# Nova_Board_Sheet.net
KiCad netlist of a schematic drawn in Altium Designer
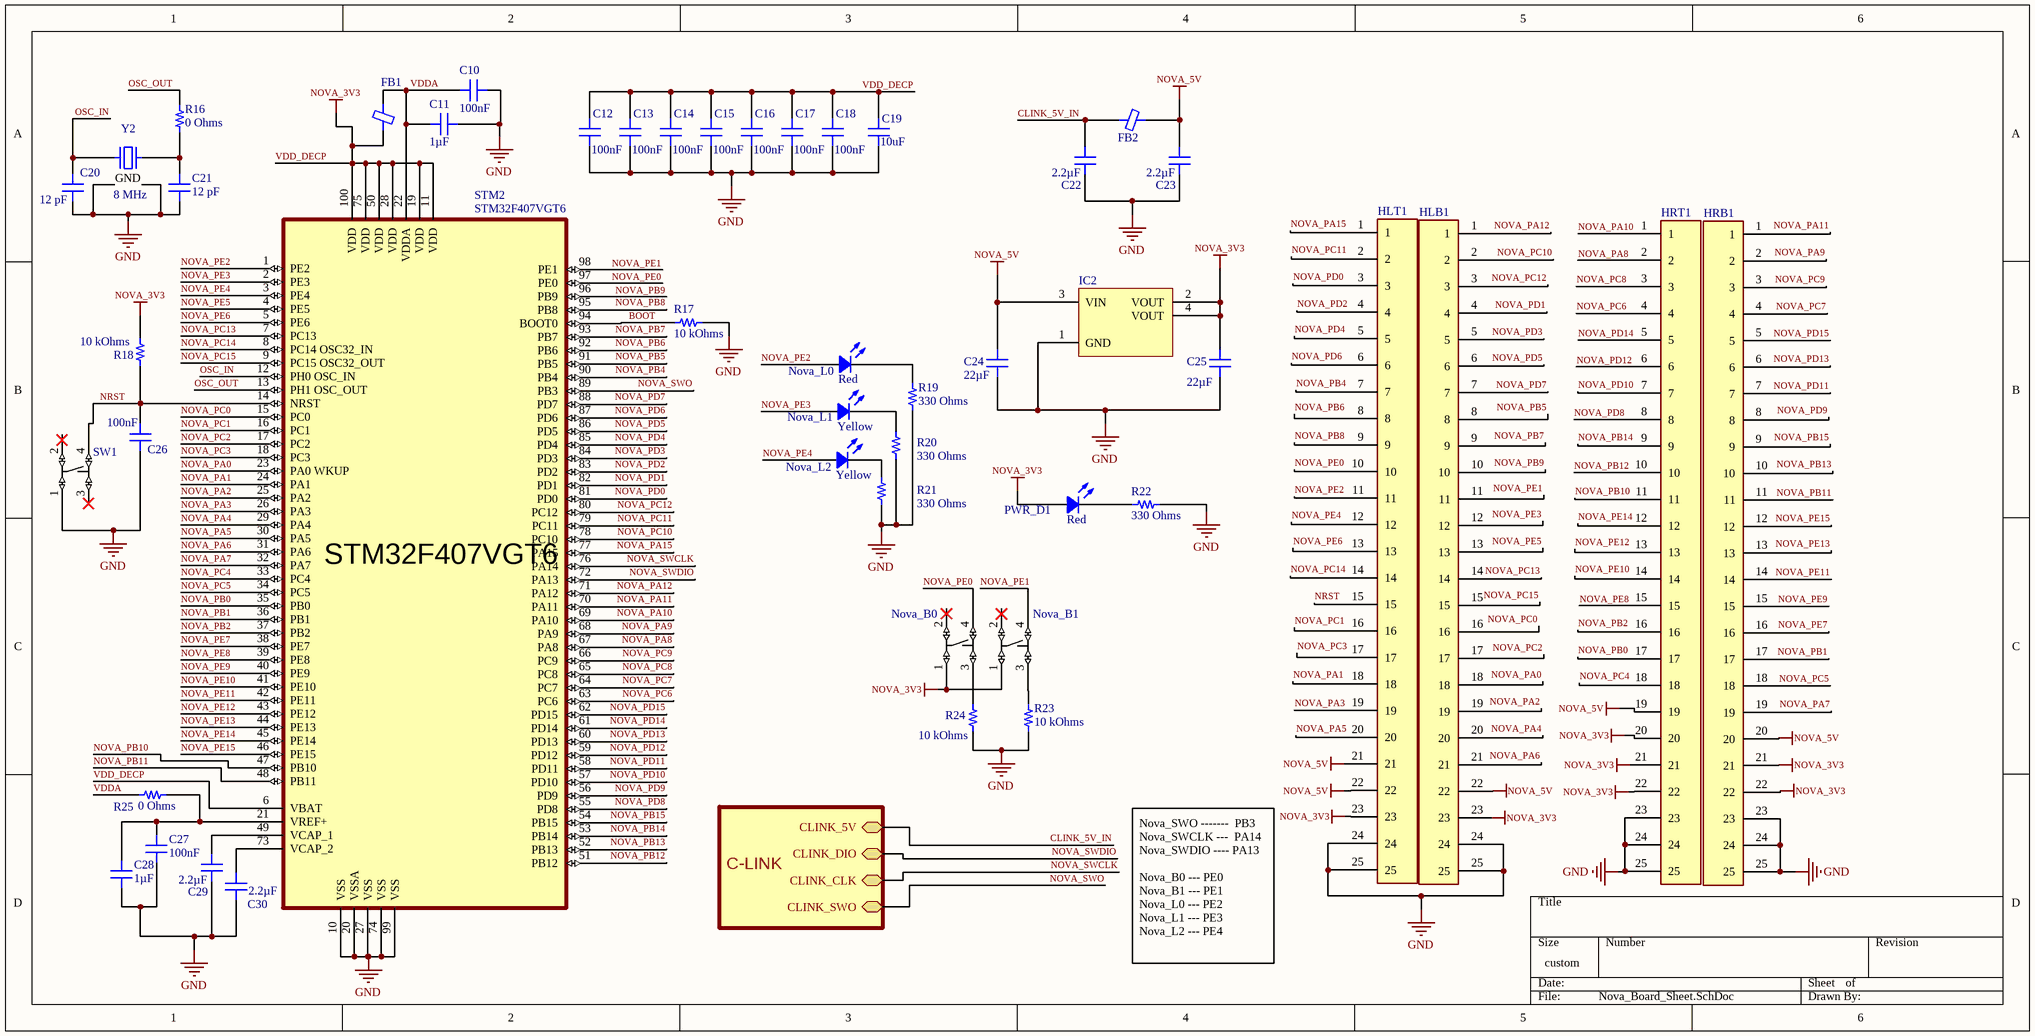
[diagram p0: Nova_Board_Sheet.SchDoc]

(export (version "E")
  (design (tool "Eeschema 10.0.6"))
  (components
    (comp (ref "C10")
      (value "0.1µF")
      (footprint "CAP 0603_1608")
      (description "CAP CER 0.1UF 100V X7R 0603")
      (fields
        (field (name "PART NUMBER") "06031C104KAT2A")
        (field (name "CAPACITANCE") "100nF")
        (field (name "MANUFACTURER") "AVX Corporation")
      )
      (libsource (lib "Celestial Altium Library - altium_library") (part "Capacitor"))
    )
    (comp (ref "C11")
      (value "1µF")
      (footprint "CAP 0603_1608")
      (description "CAP CER 0.1UF 100V X7R 0603")
      (fields
        (field (name "PART NUMBER") "06031C104KAT2A")
        (field (name "CAPACITANCE") "1µF")
        (field (name "MANUFACTURER") "AVX Corporation")
      )
      (libsource (lib "Celestial Altium Library - altium_library") (part "Capacitor"))
    )
    (comp (ref "C12")
      (value "0.1µF")
      (footprint "CAP 0603_1608")
      (description "CAP CER 0.1UF 100V X7R 0603")
      (fields
        (field (name "PART NUMBER") "06031C104KAT2A")
        (field (name "CAPACITANCE") "100nF")
        (field (name "MANUFACTURER") "AVX Corporation")
      )
      (libsource (lib "Celestial Altium Library - altium_library") (part "Capacitor"))
    )
    (comp (ref "C13")
      (value "0.1µF")
      (footprint "CAP 0603_1608")
      (description "CAP CER 0.1UF 100V X7R 0603")
      (fields
        (field (name "PART NUMBER") "06031C104KAT2A")
        (field (name "CAPACITANCE") "100nF")
        (field (name "MANUFACTURER") "AVX Corporation")
      )
      (libsource (lib "Celestial Altium Library - altium_library") (part "Capacitor"))
    )
    (comp (ref "C14")
      (value "0.1µF")
      (footprint "CAP 0603_1608")
      (description "CAP CER 0.1UF 100V X7R 0603")
      (fields
        (field (name "PART NUMBER") "06031C104KAT2A")
        (field (name "CAPACITANCE") "100nF")
        (field (name "MANUFACTURER") "AVX Corporation")
      )
      (libsource (lib "Celestial Altium Library - altium_library") (part "Capacitor"))
    )
    (comp (ref "C15")
      (value "0.1µF")
      (footprint "CAP 0603_1608")
      (description "CAP CER 0.1UF 100V X7R 0603")
      (fields
        (field (name "PART NUMBER") "06031C104KAT2A")
        (field (name "CAPACITANCE") "100nF")
        (field (name "MANUFACTURER") "AVX Corporation")
      )
      (libsource (lib "Celestial Altium Library - altium_library") (part "Capacitor"))
    )
    (comp (ref "C16")
      (value "0.1µF")
      (footprint "CAP 0603_1608")
      (description "CAP CER 0.1UF 100V X7R 0603")
      (fields
        (field (name "PART NUMBER") "06031C104KAT2A")
        (field (name "CAPACITANCE") "100nF")
        (field (name "MANUFACTURER") "AVX Corporation")
      )
      (libsource (lib "Celestial Altium Library - altium_library") (part "Capacitor"))
    )
    (comp (ref "C17")
      (value "0.1µF")
      (footprint "CAP 0603_1608")
      (description "CAP CER 0.1UF 100V X7R 0603")
      (fields
        (field (name "PART NUMBER") "06031C104KAT2A")
        (field (name "CAPACITANCE") "100nF")
        (field (name "MANUFACTURER") "AVX Corporation")
      )
      (libsource (lib "Celestial Altium Library - altium_library") (part "Capacitor"))
    )
    (comp (ref "C18")
      (value "0.1µF")
      (footprint "CAP 0603_1608")
      (description "CAP CER 0.1UF 100V X7R 0603")
      (fields
        (field (name "PART NUMBER") "06031C104KAT2A")
        (field (name "CAPACITANCE") "100nF")
        (field (name "MANUFACTURER") "AVX Corporation")
      )
      (libsource (lib "Celestial Altium Library - altium_library") (part "Capacitor"))
    )
    (comp (ref "C19")
      (value "10µF")
      (footprint "CAP 0603_1608")
      (description "CAP CER 0.1UF 100V X7R 0603")
      (fields
        (field (name "PART NUMBER") "06031C104KAT2A")
        (field (name "CAPACITANCE") "10uF")
        (field (name "MANUFACTURER") "AVX Corporation")
      )
      (libsource (lib "Celestial Altium Library - altium_library") (part "Capacitor"))
    )
    (comp (ref "C20")
      (value "12 pF")
      (footprint "CAP 0603_1608")
      (description "HIGH-Q MLCC (CF): 0603, 22 PF (1")
      (fields
        (field (name "PART NUMBER") "C06CF220F-9ZN-X0T")
        (field (name "CAPACITANCE") "12 pF")
        (field (name "MANUFACTURER") "Knowles Dielectric Labs")
      )
      (libsource (lib "Celestial Altium Library - altium_library") (part "Capacitor"))
    )
    (comp (ref "C21")
      (value "12 pF")
      (footprint "CAP 0603_1608")
      (description "HIGH-Q MLCC (CF): 0603, 22 PF (1")
      (fields
        (field (name "PART NUMBER") "C06CF220F-9ZN-X0T")
        (field (name "CAPACITANCE") "12 pF")
        (field (name "MANUFACTURER") "Knowles Dielectric Labs")
      )
      (libsource (lib "Celestial Altium Library - altium_library") (part "Capacitor"))
    )
    (comp (ref "C22")
      (value "2.2µF")
      (footprint "CAP 0603_1608")
      (description "CAP CER 0.1UF 100V X7R 0603")
      (fields
        (field (name "PART NUMBER") "06031C104KAT2A")
        (field (name "CAPACITANCE") "2.2µF")
        (field (name "MANUFACTURER") "AVX Corporation")
      )
      (libsource (lib "Celestial Altium Library - altium_library") (part "Capacitor"))
    )
    (comp (ref "C23")
      (value "2.2µF")
      (footprint "CAP 0603_1608")
      (description "CAP CER 0.1UF 100V X7R 0603")
      (fields
        (field (name "PART NUMBER") "06031C104KAT2A")
        (field (name "CAPACITANCE") "2.2µF")
        (field (name "MANUFACTURER") "AVX Corporation")
      )
      (libsource (lib "Celestial Altium Library - altium_library") (part "Capacitor"))
    )
    (comp (ref "C24")
      (value "22µF")
      (footprint "CAP 0805_2012")
      (description "CAP CER 22UF 10V X5R 0805")
      (fields
        (field (name "PART NUMBER") "0805ZD226MAT2A")
        (field (name "CAPACITANCE") "22µF")
        (field (name "MANUFACTURER") "AVX Corporation")
      )
      (libsource (lib "Celestial Altium Library - altium_library") (part "Capacitor"))
    )
    (comp (ref "C25")
      (value "22µF")
      (footprint "CAP 0805_2012")
      (description "CAP CER 22UF 10V X5R 0805")
      (fields
        (field (name "PART NUMBER") "0805ZD226MAT2A")
        (field (name "CAPACITANCE") "22µF")
        (field (name "MANUFACTURER") "AVX Corporation")
      )
      (libsource (lib "Celestial Altium Library - altium_library") (part "Capacitor"))
    )
    (comp (ref "C26")
      (value "0.1µF")
      (footprint "CAP 0603_1608")
      (description "CAP CER 0.1UF 100V X7R 0603")
      (fields
        (field (name "PART NUMBER") "06031C104KAT2A")
        (field (name "CAPACITANCE") "100nF")
        (field (name "MANUFACTURER") "AVX Corporation")
      )
      (libsource (lib "Celestial Altium Library - altium_library") (part "Capacitor"))
    )
    (comp (ref "C27")
      (value "0.1µF")
      (footprint "CAP 0603_1608")
      (description "CAP CER 0.1UF 100V X7R 0603")
      (fields
        (field (name "PART NUMBER") "06031C104KAT2A")
        (field (name "CAPACITANCE") "100nF")
        (field (name "MANUFACTURER") "AVX Corporation")
      )
      (libsource (lib "Celestial Altium Library - altium_library") (part "Capacitor"))
    )
    (comp (ref "C28")
      (value "1µF")
      (footprint "CAP 0603_1608")
      (description "CAP CER 0.1UF 100V X7R 0603")
      (fields
        (field (name "PART NUMBER") "06031C104KAT2A")
        (field (name "CAPACITANCE") "1µF")
        (field (name "MANUFACTURER") "AVX Corporation")
      )
      (libsource (lib "Celestial Altium Library - altium_library") (part "Capacitor"))
    )
    (comp (ref "C29")
      (value "2.2µF")
      (footprint "CAP 0603_1608")
      (description "CAP CER 0.1UF 100V X7R 0603")
      (fields
        (field (name "PART NUMBER") "06031C104KAT2A")
        (field (name "CAPACITANCE") "2.2µF")
        (field (name "MANUFACTURER") "AVX Corporation")
      )
      (libsource (lib "Celestial Altium Library - altium_library") (part "Capacitor"))
    )
    (comp (ref "C30")
      (value "2.2µF")
      (footprint "CAP 0603_1608")
      (description "CAP CER 0.1UF 100V X7R 0603")
      (fields
        (field (name "PART NUMBER") "06031C104KAT2A")
        (field (name "CAPACITANCE") "2.2µF")
        (field (name "MANUFACTURER") "AVX Corporation")
      )
      (libsource (lib "Celestial Altium Library - altium_library") (part "Capacitor"))
    )
    (comp (ref "FB1")
      (value "600 Ohms @ 100MHz")
      (footprint "FER 0603_1608")
      (description "FERRITEBEAD SMD Z100MHZ=600OHM 7")
      (fields
        (field (name "PART NUMBER") "BLM18DN601SZ1D")
        (field (name "MANUFACTURER") "Murata Electronics")
      )
      (libsource (lib "Celestial Altium Library - altium_library") (part "Ferrite Chip"))
    )
    (comp (ref "FB2")
      (value "600 Ohms @ 100MHz")
      (footprint "FER 0603_1608")
      (description "FERRITEBEAD SMD Z100MHZ=600OHM 7")
      (fields
        (field (name "PART NUMBER") "BLM18DN601SZ1D")
        (field (name "MANUFACTURER") "Murata Electronics")
      )
      (libsource (lib "Celestial Altium Library - altium_library") (part "Ferrite Chip"))
    )
    (comp (ref "HLB1")
      (value "2.54mm_TH_1x25_pin_header")
      (footprint "2.54mm_TH_1x25_pin_header")
      (libsource (lib "") (part "2.54mm_TH_1x25_pin_header_1"))
    )
    (comp (ref "HLT1")
      (value "2.54mm_TH_1x25_pin_header")
      (footprint "2.54mm_TH_1x25_pin_header")
      (libsource (lib "ARAF_PERSONAL_INTEGRATED_LIBRARY") (part "2.54mm_TH_1x25_pin_header"))
    )
    (comp (ref "HRB1")
      (value "2.54mm_TH_1x25_pin_header")
      (footprint "2.54mm_TH_1x25_pin_header")
      (libsource (lib "") (part "2.54mm_TH_1x25_pin_header_1"))
    )
    (comp (ref "HRT1")
      (value "2.54mm_TH_1x25_pin_header")
      (footprint "2.54mm_TH_1x25_pin_header")
      (libsource (lib "ARAF_PERSONAL_INTEGRATED_LIBRARY") (part "2.54mm_TH_1x25_pin_header"))
    )
    (comp (ref "IC2")
      (value "LDL1117S33R")
      (footprint "ST SOT-223")
      (description "IC REG LINEAR 3.3V 1.2A SOT223")
      (fields (field (name "MANUFACTURER") "STMicroelectronics"))
      (libsource (lib "Celestial Altium Library - altium_library") (part "ST LDL1117"))
    )
    (comp (ref "Nova_B0")
      (value "3x4x2.5_oval_switch")
      (footprint "3x4x2.5_oval_button_footprint")
      (libsource (lib "PushButton_Series_SCH_Library_ARAF") (part "3x4x2.5_oval_switch"))
    )
    (comp (ref "Nova_B1")
      (value "3x4x2.5_oval_switch")
      (footprint "3x4x2.5_oval_button_footprint")
      (libsource (lib "PushButton_Series_SCH_Library_ARAF") (part "3x4x2.5_oval_switch"))
    )
    (comp (ref "Nova_L0")
      (value "Red")
      (footprint "LED 0603_1608 RED")
      (description "LED RED DIFFUSED 1608 SMD")
      (fields
        (field (name "PART NUMBER") "VFHR1111C-3BY2A-TR")
        (field (name "MANUFACTURER") "Stanley Electric Co")
      )
      (libsource (lib "Celestial Altium Library - altium_library") (part "LED"))
    )
    (comp (ref "Nova_L1")
      (value "Yellow")
      (footprint "LED 0603_1608 YELLOW")
      (description "LED YELLOW 0603 SMD")
      (fields (field (name "PART NUMBER") "5973405507F") (field (name "MANUFACTURER") "Dialight"))
      (libsource (lib "Celestial Altium Library - altium_library") (part "LED"))
    )
    (comp (ref "Nova_L2")
      (value "Yellow")
      (footprint "LED 0603_1608 YELLOW")
      (description "LED YELLOW 0603 SMD")
      (fields (field (name "PART NUMBER") "5973405507F") (field (name "MANUFACTURER") "Dialight"))
      (libsource (lib "Celestial Altium Library - altium_library") (part "LED"))
    )
    (comp (ref "PWR_D1")
      (value "Red")
      (footprint "LED 0603_1608 RED")
      (description "LED RED DIFFUSED 1608 SMD")
      (fields
        (field (name "PART NUMBER") "VFHR1111C-3BY2A-TR")
        (field (name "MANUFACTURER") "Stanley Electric Co")
      )
      (libsource (lib "Celestial Altium Library - altium_library") (part "LED"))
    )
    (comp (ref "R16")
      (value "0 Ohms")
      (footprint "RES 0603_1608")
      (description "RES 0 OHM JUMPER 0603")
      (fields
        (field (name "PART NUMBER") "TLRZ1JTTD")
        (field (name "MANUFACTURER") "KOA Speer Electronics, Inc.")
      )
      (libsource (lib "Celestial Altium Library - altium_library") (part "Resistor"))
    )
    (comp (ref "R17")
      (value "10 kOhms")
      (footprint "RES 0603_1608")
      (description "RES 10K OHM 0.1% 1/16W 0603")
      (fields
        (field (name "PART NUMBER") "RNCS0603BKE10K0")
        (field (name "MANUFACTURER") "Stackpole Electronics Inc")
      )
      (libsource (lib "Celestial Altium Library - altium_library") (part "Resistor"))
    )
    (comp (ref "R18")
      (value "10 kOhms")
      (footprint "RES 0603_1608")
      (description "RES 10K OHM 0.1% 1/16W 0603")
      (fields
        (field (name "PART NUMBER") "RNCS0603BKE10K0")
        (field (name "MANUFACTURER") "Stackpole Electronics Inc")
      )
      (libsource (lib "Celestial Altium Library - altium_library") (part "Resistor"))
    )
    (comp (ref "R19")
      (value "330 Ohms")
      (footprint "RES 0603_1608")
      (description "RES 10K OHM 0.1% 1/16W 0603")
      (fields
        (field (name "PART NUMBER") "RNCS0603BKE10K0")
        (field (name "MANUFACTURER") "Stackpole Electronics Inc")
      )
      (libsource (lib "Celestial Altium Library - altium_library") (part "Resistor"))
    )
    (comp (ref "R20")
      (value "330 Ohms")
      (footprint "RES 0603_1608")
      (description "RES 10K OHM 0.1% 1/16W 0603")
      (fields
        (field (name "PART NUMBER") "RNCS0603BKE10K0")
        (field (name "MANUFACTURER") "Stackpole Electronics Inc")
      )
      (libsource (lib "Celestial Altium Library - altium_library") (part "Resistor"))
    )
    (comp (ref "R21")
      (value "330 Ohms")
      (footprint "RES 0603_1608")
      (description "RES 10K OHM 0.1% 1/16W 0603")
      (fields
        (field (name "PART NUMBER") "RNCS0603BKE10K0")
        (field (name "MANUFACTURER") "Stackpole Electronics Inc")
      )
      (libsource (lib "Celestial Altium Library - altium_library") (part "Resistor"))
    )
    (comp (ref "R22")
      (value "330 Ohms")
      (footprint "RES 0603_1608")
      (description "RES 10K OHM 0.1% 1/16W 0603")
      (fields
        (field (name "PART NUMBER") "RNCS0603BKE10K0")
        (field (name "MANUFACTURER") "Stackpole Electronics Inc")
      )
      (libsource (lib "Celestial Altium Library - altium_library") (part "Resistor"))
    )
    (comp (ref "R23")
      (value "10 kOhms")
      (footprint "RES 0603_1608")
      (description "RES 10K OHM 0.1% 1/16W 0603")
      (fields
        (field (name "PART NUMBER") "RNCS0603BKE10K0")
        (field (name "MANUFACTURER") "Stackpole Electronics Inc")
      )
      (libsource (lib "Celestial Altium Library - altium_library") (part "Resistor"))
    )
    (comp (ref "R24")
      (value "10 kOhms")
      (footprint "RES 0603_1608")
      (description "RES 10K OHM 0.1% 1/16W 0603")
      (fields
        (field (name "PART NUMBER") "RNCS0603BKE10K0")
        (field (name "MANUFACTURER") "Stackpole Electronics Inc")
      )
      (libsource (lib "Celestial Altium Library - altium_library") (part "Resistor"))
    )
    (comp (ref "R25")
      (value "0 Ohms")
      (footprint "RES 0603_1608")
      (description "RES 0 OHM JUMPER 0603")
      (fields
        (field (name "PART NUMBER") "TLRZ1JTTD")
        (field (name "MANUFACTURER") "KOA Speer Electronics, Inc.")
      )
      (libsource (lib "Celestial Altium Library - altium_library") (part "Resistor"))
    )
    (comp (ref "STM2")
      (value "STM32F407VGT6")
      (footprint "STM32F407VGT6_FOOTPRINT")
      (description "1MB 1.8V~3.6V ARM-M4 192KB 168MHz FLASH 82 LQFP-100(14x14) Microcontrollers (MCU/MPU/SOC) ROHS")
      (fields (field (name "JLCPCB PART #") "C12345"))
      (libsource (lib "STM32F_Series_SCH_Library_ARAF") (part "STM32F407VGT6"))
    )
    (comp (ref "SW1")
      (value "3x4x2.5_oval_switch")
      (footprint "3x4x2.5_oval_button_footprint")
      (libsource (lib "PushButton_Series_SCH_Library_ARAF") (part "3x4x2.5_oval_switch"))
    )
    (comp (ref "Y2")
      (value "8 MHz")
      (footprint "EPSON TSX-3225")
      (description "CRYSTAL 16.0000MHZ 16PF SMD")
      (fields (field (name "PART NUMBER") "TSX-3225 16.0000MF10U-B0") (field (name "MANUFACTURER") "EPSON"))
      (libsource (lib "Celestial Altium Library - altium_library") (part "Epson Crystal TSX-3225"))
    )
  )
  (nets
    (net (code "1") (name "/BOOT") (class "Default")
      (node (ref "R17") (pin "2") (pinfunction "2_2") (pintype "passive"))
      (node (ref "STM2") (pin "94") (pinfunction "BOOT0_94") (pintype "bidirectional"))
    )
    (net (code "2") (name "/CLINK_5V_IN") (class "Default")
      (node (ref "C22") (pin "1") (pinfunction "1_1") (pintype "passive"))
      (node (ref "FB2") (pin "2") (pinfunction "2_2") (pintype "passive"))
    )
    (net (code "3") (name "/NOVA_PA0") (class "Default")
      (node (ref "HLB1") (pin "18") (pinfunction "18_18") (pintype "passive"))
      (node (ref "STM2") (pin "23") (pinfunction "PA0_WKUP_23") (pintype "bidirectional"))
    )
    (net (code "4") (name "/NOVA_PA1") (class "Default")
      (node (ref "HLT1") (pin "18") (pinfunction "18_18") (pintype "passive"))
      (node (ref "STM2") (pin "24") (pinfunction "PA1_24") (pintype "bidirectional"))
    )
    (net (code "5") (name "/NOVA_PA2") (class "Default")
      (node (ref "HLB1") (pin "19") (pinfunction "19_19") (pintype "passive"))
      (node (ref "STM2") (pin "25") (pinfunction "PA2_25") (pintype "bidirectional"))
    )
    (net (code "6") (name "/NOVA_PA3") (class "Default")
      (node (ref "HLT1") (pin "19") (pinfunction "19_19") (pintype "passive"))
      (node (ref "STM2") (pin "26") (pinfunction "PA3_26") (pintype "bidirectional"))
    )
    (net (code "7") (name "/NOVA_PA4") (class "Default")
      (node (ref "HLB1") (pin "20") (pinfunction "20_20") (pintype "passive"))
      (node (ref "STM2") (pin "29") (pinfunction "PA4_29") (pintype "bidirectional"))
    )
    (net (code "8") (name "/NOVA_PA5") (class "Default")
      (node (ref "HLT1") (pin "20") (pinfunction "20_20") (pintype "passive"))
      (node (ref "STM2") (pin "30") (pinfunction "PA5_30") (pintype "bidirectional"))
    )
    (net (code "9") (name "/NOVA_PA6") (class "Default")
      (node (ref "HLB1") (pin "21") (pinfunction "21_21") (pintype "passive"))
      (node (ref "STM2") (pin "31") (pinfunction "PA6_31") (pintype "bidirectional"))
    )
    (net (code "10") (name "/NOVA_PA7") (class "Default")
      (node (ref "HRB1") (pin "19") (pinfunction "19_19") (pintype "passive"))
      (node (ref "STM2") (pin "32") (pinfunction "PA7_32") (pintype "bidirectional"))
    )
    (net (code "11") (name "/NOVA_PA8") (class "Default")
      (node (ref "HRT1") (pin "2") (pinfunction "2_2") (pintype "passive"))
      (node (ref "STM2") (pin "67") (pinfunction "PA8_67") (pintype "bidirectional"))
    )
    (net (code "12") (name "/NOVA_PA9") (class "Default")
      (node (ref "HRB1") (pin "2") (pinfunction "2_2") (pintype "passive"))
      (node (ref "STM2") (pin "68") (pinfunction "PA9_68") (pintype "bidirectional"))
    )
    (net (code "13") (name "/NOVA_PA10") (class "Default")
      (node (ref "HRT1") (pin "1") (pinfunction "1_1") (pintype "passive"))
      (node (ref "STM2") (pin "69") (pinfunction "PA10_69") (pintype "bidirectional"))
    )
    (net (code "14") (name "/NOVA_PA11") (class "Default")
      (node (ref "HRB1") (pin "1") (pinfunction "1_1") (pintype "passive"))
      (node (ref "STM2") (pin "70") (pinfunction "PA11_70") (pintype "bidirectional"))
    )
    (net (code "15") (name "/NOVA_PA12") (class "Default")
      (node (ref "HLB1") (pin "1") (pinfunction "1_1") (pintype "passive"))
      (node (ref "STM2") (pin "71") (pinfunction "PA12_71") (pintype "bidirectional"))
    )
    (net (code "16") (name "/NOVA_PA15") (class "Default")
      (node (ref "HLT1") (pin "1") (pinfunction "1_1") (pintype "passive"))
      (node (ref "STM2") (pin "77") (pinfunction "PA15_77") (pintype "bidirectional"))
    )
    (net (code "17") (name "/NOVA_PB0") (class "Default")
      (node (ref "HRT1") (pin "17") (pinfunction "17_17") (pintype "passive"))
      (node (ref "STM2") (pin "35") (pinfunction "PB0_35") (pintype "bidirectional"))
    )
    (net (code "18") (name "/NOVA_PB1") (class "Default")
      (node (ref "HRB1") (pin "17") (pinfunction "17_17") (pintype "passive"))
      (node (ref "STM2") (pin "36") (pinfunction "PB1_36") (pintype "bidirectional"))
    )
    (net (code "19") (name "/NOVA_PB2") (class "Default")
      (node (ref "HRT1") (pin "16") (pinfunction "16_16") (pintype "passive"))
      (node (ref "STM2") (pin "37") (pinfunction "PB2_37") (pintype "bidirectional"))
    )
    (net (code "20") (name "/NOVA_PB4") (class "Default")
      (node (ref "HLT1") (pin "7") (pinfunction "7_7") (pintype "passive"))
      (node (ref "STM2") (pin "90") (pinfunction "PB4_90") (pintype "bidirectional"))
    )
    (net (code "21") (name "/NOVA_PB5") (class "Default")
      (node (ref "HLB1") (pin "8") (pinfunction "8_8") (pintype "passive"))
      (node (ref "STM2") (pin "91") (pinfunction "PB5_91") (pintype "bidirectional"))
    )
    (net (code "22") (name "/NOVA_PB6") (class "Default")
      (node (ref "HLT1") (pin "8") (pinfunction "8_8") (pintype "passive"))
      (node (ref "STM2") (pin "92") (pinfunction "PB6_92") (pintype "bidirectional"))
    )
    (net (code "23") (name "/NOVA_PB7") (class "Default")
      (node (ref "HLB1") (pin "9") (pinfunction "9_9") (pintype "passive"))
      (node (ref "STM2") (pin "93") (pinfunction "PB7_93") (pintype "bidirectional"))
    )
    (net (code "24") (name "/NOVA_PB8") (class "Default")
      (node (ref "HLT1") (pin "9") (pinfunction "9_9") (pintype "passive"))
      (node (ref "STM2") (pin "95") (pinfunction "PB8_95") (pintype "bidirectional"))
    )
    (net (code "25") (name "/NOVA_PB9") (class "Default")
      (node (ref "HLB1") (pin "10") (pinfunction "10_10") (pintype "passive"))
      (node (ref "STM2") (pin "96") (pinfunction "PB9_96") (pintype "bidirectional"))
    )
    (net (code "26") (name "/NOVA_PB10") (class "Default")
      (node (ref "HRT1") (pin "11") (pinfunction "11_11") (pintype "passive"))
      (node (ref "STM2") (pin "47") (pinfunction "PB10_47") (pintype "bidirectional"))
    )
    (net (code "27") (name "/NOVA_PB11") (class "Default")
      (node (ref "HRB1") (pin "11") (pinfunction "11_11") (pintype "passive"))
      (node (ref "STM2") (pin "48") (pinfunction "PB11_48") (pintype "bidirectional"))
    )
    (net (code "28") (name "/NOVA_PB12") (class "Default")
      (node (ref "HRT1") (pin "10") (pinfunction "10_10") (pintype "passive"))
      (node (ref "STM2") (pin "51") (pinfunction "PB12_51") (pintype "bidirectional"))
    )
    (net (code "29") (name "/NOVA_PB13") (class "Default")
      (node (ref "HRB1") (pin "10") (pinfunction "10_10") (pintype "passive"))
      (node (ref "STM2") (pin "52") (pinfunction "PB13_52") (pintype "bidirectional"))
    )
    (net (code "30") (name "/NOVA_PB14") (class "Default")
      (node (ref "HRT1") (pin "9") (pinfunction "9_9") (pintype "passive"))
      (node (ref "STM2") (pin "53") (pinfunction "PB14_53") (pintype "bidirectional"))
    )
    (net (code "31") (name "/NOVA_PB15") (class "Default")
      (node (ref "HRB1") (pin "9") (pinfunction "9_9") (pintype "passive"))
      (node (ref "STM2") (pin "54") (pinfunction "PB15_54") (pintype "bidirectional"))
    )
    (net (code "32") (name "/NOVA_PC0") (class "Default")
      (node (ref "HLB1") (pin "16") (pinfunction "16_16") (pintype "passive"))
      (node (ref "STM2") (pin "15") (pinfunction "PC0_15") (pintype "bidirectional"))
    )
    (net (code "33") (name "/NOVA_PC1") (class "Default")
      (node (ref "HLT1") (pin "16") (pinfunction "16_16") (pintype "passive"))
      (node (ref "STM2") (pin "16") (pinfunction "PC1_16") (pintype "bidirectional"))
    )
    (net (code "34") (name "/NOVA_PC2") (class "Default")
      (node (ref "HLB1") (pin "17") (pinfunction "17_17") (pintype "passive"))
      (node (ref "STM2") (pin "17") (pinfunction "PC2_17") (pintype "bidirectional"))
    )
    (net (code "35") (name "/NOVA_PC3") (class "Default")
      (node (ref "HLT1") (pin "17") (pinfunction "17_17") (pintype "passive"))
      (node (ref "STM2") (pin "18") (pinfunction "PC3_18") (pintype "bidirectional"))
    )
    (net (code "36") (name "/NOVA_PC4") (class "Default")
      (node (ref "HRT1") (pin "18") (pinfunction "18_18") (pintype "passive"))
      (node (ref "STM2") (pin "33") (pinfunction "PC4_33") (pintype "bidirectional"))
    )
    (net (code "37") (name "/NOVA_PC5") (class "Default")
      (node (ref "HRB1") (pin "18") (pinfunction "18_18") (pintype "passive"))
      (node (ref "STM2") (pin "34") (pinfunction "PC5_34") (pintype "bidirectional"))
    )
    (net (code "38") (name "/NOVA_PC6") (class "Default")
      (node (ref "HRT1") (pin "4") (pinfunction "4_4") (pintype "passive"))
      (node (ref "STM2") (pin "63") (pinfunction "PC6_63") (pintype "bidirectional"))
    )
    (net (code "39") (name "/NOVA_PC7") (class "Default")
      (node (ref "HRB1") (pin "4") (pinfunction "4_4") (pintype "passive"))
      (node (ref "STM2") (pin "64") (pinfunction "PC7_64") (pintype "bidirectional"))
    )
    (net (code "40") (name "/NOVA_PC8") (class "Default")
      (node (ref "HRT1") (pin "3") (pinfunction "3_3") (pintype "passive"))
      (node (ref "STM2") (pin "65") (pinfunction "PC8_65") (pintype "bidirectional"))
    )
    (net (code "41") (name "/NOVA_PC9") (class "Default")
      (node (ref "HRB1") (pin "3") (pinfunction "3_3") (pintype "passive"))
      (node (ref "STM2") (pin "66") (pinfunction "PC9_66") (pintype "bidirectional"))
    )
    (net (code "42") (name "/NOVA_PC10") (class "Default")
      (node (ref "HLB1") (pin "2") (pinfunction "2_2") (pintype "passive"))
      (node (ref "STM2") (pin "78") (pinfunction "PC10_78") (pintype "bidirectional"))
    )
    (net (code "43") (name "/NOVA_PC11") (class "Default")
      (node (ref "HLT1") (pin "2") (pinfunction "2_2") (pintype "passive"))
      (node (ref "STM2") (pin "79") (pinfunction "PC11_79") (pintype "bidirectional"))
    )
    (net (code "44") (name "/NOVA_PC12") (class "Default")
      (node (ref "HLB1") (pin "3") (pinfunction "3_3") (pintype "passive"))
      (node (ref "STM2") (pin "80") (pinfunction "PC12_80") (pintype "bidirectional"))
    )
    (net (code "45") (name "/NOVA_PC13") (class "Default")
      (node (ref "HLB1") (pin "14") (pinfunction "14_14") (pintype "passive"))
      (node (ref "STM2") (pin "7") (pinfunction "PC13_7") (pintype "bidirectional"))
    )
    (net (code "46") (name "/NOVA_PC14") (class "Default")
      (node (ref "HLT1") (pin "14") (pinfunction "14_14") (pintype "passive"))
      (node (ref "STM2") (pin "8") (pinfunction "PC14_OSC32_IN_8") (pintype "bidirectional"))
    )
    (net (code "47") (name "/NOVA_PC15") (class "Default")
      (node (ref "HLB1") (pin "15") (pinfunction "15_15") (pintype "passive"))
      (node (ref "STM2") (pin "9") (pinfunction "PC15_OSC32_OUT_9") (pintype "bidirectional"))
    )
    (net (code "48") (name "/NOVA_PD0") (class "Default")
      (node (ref "HLT1") (pin "3") (pinfunction "3_3") (pintype "passive"))
      (node (ref "STM2") (pin "81") (pinfunction "PD0_81") (pintype "bidirectional"))
    )
    (net (code "49") (name "/NOVA_PD1") (class "Default")
      (node (ref "HLB1") (pin "4") (pinfunction "4_4") (pintype "passive"))
      (node (ref "STM2") (pin "82") (pinfunction "PD1_82") (pintype "bidirectional"))
    )
    (net (code "50") (name "/NOVA_PD2") (class "Default")
      (node (ref "HLT1") (pin "4") (pinfunction "4_4") (pintype "passive"))
      (node (ref "STM2") (pin "83") (pinfunction "PD2_83") (pintype "bidirectional"))
    )
    (net (code "51") (name "/NOVA_PD3") (class "Default")
      (node (ref "HLB1") (pin "5") (pinfunction "5_5") (pintype "passive"))
      (node (ref "STM2") (pin "84") (pinfunction "PD3_84") (pintype "bidirectional"))
    )
    (net (code "52") (name "/NOVA_PD4") (class "Default")
      (node (ref "HLT1") (pin "5") (pinfunction "5_5") (pintype "passive"))
      (node (ref "STM2") (pin "85") (pinfunction "PD4_85") (pintype "bidirectional"))
    )
    (net (code "53") (name "/NOVA_PD5") (class "Default")
      (node (ref "HLB1") (pin "6") (pinfunction "6_6") (pintype "passive"))
      (node (ref "STM2") (pin "86") (pinfunction "PD5_86") (pintype "bidirectional"))
    )
    (net (code "54") (name "/NOVA_PD6") (class "Default")
      (node (ref "HLT1") (pin "6") (pinfunction "6_6") (pintype "passive"))
      (node (ref "STM2") (pin "87") (pinfunction "PD6_87") (pintype "bidirectional"))
    )
    (net (code "55") (name "/NOVA_PD7") (class "Default")
      (node (ref "HLB1") (pin "7") (pinfunction "7_7") (pintype "passive"))
      (node (ref "STM2") (pin "88") (pinfunction "PD7_88") (pintype "bidirectional"))
    )
    (net (code "56") (name "/NOVA_PD8") (class "Default")
      (node (ref "HRT1") (pin "8") (pinfunction "8_8") (pintype "passive"))
      (node (ref "STM2") (pin "55") (pinfunction "PD8_55") (pintype "bidirectional"))
    )
    (net (code "57") (name "/NOVA_PD9") (class "Default")
      (node (ref "HRB1") (pin "8") (pinfunction "8_8") (pintype "passive"))
      (node (ref "STM2") (pin "56") (pinfunction "PD9_56") (pintype "bidirectional"))
    )
    (net (code "58") (name "/NOVA_PD10") (class "Default")
      (node (ref "HRT1") (pin "7") (pinfunction "7_7") (pintype "passive"))
      (node (ref "STM2") (pin "57") (pinfunction "PD10_57") (pintype "bidirectional"))
    )
    (net (code "59") (name "/NOVA_PD11") (class "Default")
      (node (ref "HRB1") (pin "7") (pinfunction "7_7") (pintype "passive"))
      (node (ref "STM2") (pin "58") (pinfunction "PD11_58") (pintype "bidirectional"))
    )
    (net (code "60") (name "/NOVA_PD12") (class "Default")
      (node (ref "HRT1") (pin "6") (pinfunction "6_6") (pintype "passive"))
      (node (ref "STM2") (pin "59") (pinfunction "PD12_59") (pintype "bidirectional"))
    )
    (net (code "61") (name "/NOVA_PD13") (class "Default")
      (node (ref "HRB1") (pin "6") (pinfunction "6_6") (pintype "passive"))
      (node (ref "STM2") (pin "60") (pinfunction "PD13_60") (pintype "bidirectional"))
    )
    (net (code "62") (name "/NOVA_PD14") (class "Default")
      (node (ref "HRT1") (pin "5") (pinfunction "5_5") (pintype "passive"))
      (node (ref "STM2") (pin "61") (pinfunction "PD14_61") (pintype "bidirectional"))
    )
    (net (code "63") (name "/NOVA_PD15") (class "Default")
      (node (ref "HRB1") (pin "5") (pinfunction "5_5") (pintype "passive"))
      (node (ref "STM2") (pin "62") (pinfunction "PD15_62") (pintype "bidirectional"))
    )
    (net (code "64") (name "/NOVA_PE0") (class "Default")
      (node (ref "HLT1") (pin "10") (pinfunction "10_10") (pintype "passive"))
      (node (ref "Nova_B0") (pin "4") (pinfunction "4_4") (pintype "bidirectional"))
      (node (ref "STM2") (pin "97") (pinfunction "PE0_97") (pintype "bidirectional"))
    )
    (net (code "65") (name "/NOVA_PE1") (class "Default")
      (node (ref "HLB1") (pin "11") (pinfunction "11_11") (pintype "passive"))
      (node (ref "Nova_B1") (pin "4") (pinfunction "4_4") (pintype "bidirectional"))
      (node (ref "STM2") (pin "98") (pinfunction "PE1_98") (pintype "bidirectional"))
    )
    (net (code "66") (name "/NOVA_PE2") (class "Default")
      (node (ref "HLT1") (pin "11") (pinfunction "11_11") (pintype "passive"))
      (node (ref "Nova_L0") (pin "1") (pinfunction "1_1") (pintype "passive"))
      (node (ref "STM2") (pin "1") (pinfunction "PE2_1") (pintype "bidirectional"))
    )
    (net (code "67") (name "/NOVA_PE3") (class "Default")
      (node (ref "HLB1") (pin "12") (pinfunction "12_12") (pintype "passive"))
      (node (ref "Nova_L1") (pin "1") (pinfunction "1_1") (pintype "passive"))
      (node (ref "STM2") (pin "2") (pinfunction "PE3_2") (pintype "bidirectional"))
    )
    (net (code "68") (name "/NOVA_PE4") (class "Default")
      (node (ref "HLT1") (pin "12") (pinfunction "12_12") (pintype "passive"))
      (node (ref "Nova_L2") (pin "1") (pinfunction "1_1") (pintype "passive"))
      (node (ref "STM2") (pin "3") (pinfunction "PE4_3") (pintype "bidirectional"))
    )
    (net (code "69") (name "/NOVA_PE5") (class "Default")
      (node (ref "HLB1") (pin "13") (pinfunction "13_13") (pintype "passive"))
      (node (ref "STM2") (pin "4") (pinfunction "PE5_4") (pintype "bidirectional"))
    )
    (net (code "70") (name "/NOVA_PE6") (class "Default")
      (node (ref "HLT1") (pin "13") (pinfunction "13_13") (pintype "passive"))
      (node (ref "STM2") (pin "5") (pinfunction "PE6_5") (pintype "bidirectional"))
    )
    (net (code "71") (name "/NOVA_PE7") (class "Default")
      (node (ref "HRB1") (pin "16") (pinfunction "16_16") (pintype "passive"))
      (node (ref "STM2") (pin "38") (pinfunction "PE7_38") (pintype "bidirectional"))
    )
    (net (code "72") (name "/NOVA_PE8") (class "Default")
      (node (ref "HRT1") (pin "15") (pinfunction "15_15") (pintype "passive"))
      (node (ref "STM2") (pin "39") (pinfunction "PE8_39") (pintype "bidirectional"))
    )
    (net (code "73") (name "/NOVA_PE9") (class "Default")
      (node (ref "HRB1") (pin "15") (pinfunction "15_15") (pintype "passive"))
      (node (ref "STM2") (pin "40") (pinfunction "PE9_40") (pintype "bidirectional"))
    )
    (net (code "74") (name "/NOVA_PE10") (class "Default")
      (node (ref "HRT1") (pin "14") (pinfunction "14_14") (pintype "passive"))
      (node (ref "STM2") (pin "41") (pinfunction "PE10_41") (pintype "bidirectional"))
    )
    (net (code "75") (name "/NOVA_PE11") (class "Default")
      (node (ref "HRB1") (pin "14") (pinfunction "14_14") (pintype "passive"))
      (node (ref "STM2") (pin "42") (pinfunction "PE11_42") (pintype "bidirectional"))
    )
    (net (code "76") (name "/NOVA_PE12") (class "Default")
      (node (ref "HRT1") (pin "13") (pinfunction "13_13") (pintype "passive"))
      (node (ref "STM2") (pin "43") (pinfunction "PE12_43") (pintype "bidirectional"))
    )
    (net (code "77") (name "/NOVA_PE13") (class "Default")
      (node (ref "HRB1") (pin "13") (pinfunction "13_13") (pintype "passive"))
      (node (ref "STM2") (pin "44") (pinfunction "PE13_44") (pintype "bidirectional"))
    )
    (net (code "78") (name "/NOVA_PE14") (class "Default")
      (node (ref "HRT1") (pin "12") (pinfunction "12_12") (pintype "passive"))
      (node (ref "STM2") (pin "45") (pinfunction "PE14_45") (pintype "bidirectional"))
    )
    (net (code "79") (name "/NOVA_PE15") (class "Default")
      (node (ref "HRB1") (pin "12") (pinfunction "12_12") (pintype "passive"))
      (node (ref "STM2") (pin "46") (pinfunction "PE15_46") (pintype "bidirectional"))
    )
    (net (code "80") (name "/NOVA_SWCLK") (class "Default")
      (node (ref "STM2") (pin "76") (pinfunction "PA14_76") (pintype "bidirectional"))
    )
    (net (code "81") (name "/NOVA_SWDIO") (class "Default")
      (node (ref "STM2") (pin "72") (pinfunction "PA13_72") (pintype "bidirectional"))
    )
    (net (code "82") (name "/NOVA_SWO") (class "Default")
      (node (ref "STM2") (pin "89") (pinfunction "PB3_89") (pintype "bidirectional"))
    )
    (net (code "83") (name "/NRST") (class "Default")
      (node (ref "C26") (pin "2") (pinfunction "2_2") (pintype "passive"))
      (node (ref "HLT1") (pin "15") (pinfunction "15_15") (pintype "passive"))
      (node (ref "R18") (pin "2") (pinfunction "2_2") (pintype "passive"))
      (node (ref "STM2") (pin "14") (pinfunction "NRST_14") (pintype "bidirectional"))
      (node (ref "SW1") (pin "4") (pinfunction "4_4") (pintype "bidirectional"))
    )
    (net (code "84") (name "/OSC_IN") (class "Default")
      (node (ref "C20") (pin "2") (pinfunction "2_2") (pintype "passive"))
      (node (ref "STM2") (pin "12") (pinfunction "PH0_OSC_IN_12") (pintype "bidirectional"))
      (node (ref "Y2") (pin "1") (pinfunction "1_1") (pintype "passive"))
    )
    (net (code "85") (name "/OSC_OUT") (class "Default")
      (node (ref "R16") (pin "2") (pinfunction "2_2") (pintype "passive"))
      (node (ref "STM2") (pin "13") (pinfunction "PH1_OSC_OUT_13") (pintype "bidirectional"))
    )
    (net (code "86") (name "/VDDA") (class "Default")
      (node (ref "C10") (pin "2") (pinfunction "2_2") (pintype "passive"))
      (node (ref "C11") (pin "2") (pinfunction "2_2") (pintype "passive"))
      (node (ref "FB1") (pin "2") (pinfunction "2_2") (pintype "passive"))
      (node (ref "R25") (pin "1") (pinfunction "1_1") (pintype "passive"))
      (node (ref "STM2") (pin "22") (pinfunction "VDDA_22") (pintype "power_in"))
    )
    (net (code "87") (name "GND") (class "Default")
      (node (ref "C10") (pin "1") (pinfunction "1_1") (pintype "passive"))
      (node (ref "C11") (pin "1") (pinfunction "1_1") (pintype "passive"))
      (node (ref "C12") (pin "2") (pinfunction "2_2") (pintype "passive"))
      (node (ref "C13") (pin "2") (pinfunction "2_2") (pintype "passive"))
      (node (ref "C14") (pin "2") (pinfunction "2_2") (pintype "passive"))
      (node (ref "C15") (pin "2") (pinfunction "2_2") (pintype "passive"))
      (node (ref "C16") (pin "2") (pinfunction "2_2") (pintype "passive"))
      (node (ref "C17") (pin "2") (pinfunction "2_2") (pintype "passive"))
      (node (ref "C18") (pin "2") (pinfunction "2_2") (pintype "passive"))
      (node (ref "C19") (pin "1") (pinfunction "1_1") (pintype "passive"))
      (node (ref "C20") (pin "1") (pinfunction "1_1") (pintype "passive"))
      (node (ref "C21") (pin "1") (pinfunction "1_1") (pintype "passive"))
      (node (ref "C22") (pin "2") (pinfunction "2_2") (pintype "passive"))
      (node (ref "C23") (pin "2") (pinfunction "2_2") (pintype "passive"))
      (node (ref "C24") (pin "1") (pinfunction "1_1") (pintype "passive"))
      (node (ref "C25") (pin "1") (pinfunction "1_1") (pintype "passive"))
      (node (ref "C26") (pin "1") (pinfunction "1_1") (pintype "passive"))
      (node (ref "C27") (pin "2") (pinfunction "2_2") (pintype "passive"))
      (node (ref "C28") (pin "2") (pinfunction "2_2") (pintype "passive"))
      (node (ref "C29") (pin "2") (pinfunction "2_2") (pintype "passive"))
      (node (ref "C30") (pin "2") (pinfunction "2_2") (pintype "passive"))
      (node (ref "HLB1") (pin "24") (pinfunction "24_24") (pintype "passive"))
      (node (ref "HLB1") (pin "25") (pinfunction "25_25") (pintype "passive"))
      (node (ref "HLT1") (pin "24") (pinfunction "24_24") (pintype "passive"))
      (node (ref "HLT1") (pin "25") (pinfunction "25_25") (pintype "passive"))
      (node (ref "HRB1") (pin "23") (pinfunction "23_23") (pintype "passive"))
      (node (ref "HRB1") (pin "24") (pinfunction "24_24") (pintype "passive"))
      (node (ref "HRB1") (pin "25") (pinfunction "25_25") (pintype "passive"))
      (node (ref "HRT1") (pin "23") (pinfunction "23_23") (pintype "passive"))
      (node (ref "HRT1") (pin "24") (pinfunction "24_24") (pintype "passive"))
      (node (ref "HRT1") (pin "25") (pinfunction "25_25") (pintype "passive"))
      (node (ref "IC2") (pin "1") (pinfunction "GND_1") (pintype "passive"))
      (node (ref "R17") (pin "1") (pinfunction "1_1") (pintype "passive"))
      (node (ref "R19") (pin "1") (pinfunction "1_1") (pintype "passive"))
      (node (ref "R20") (pin "1") (pinfunction "1_1") (pintype "passive"))
      (node (ref "R21") (pin "1") (pinfunction "1_1") (pintype "passive"))
      (node (ref "R22") (pin "2") (pinfunction "2_2") (pintype "passive"))
      (node (ref "R23") (pin "2") (pinfunction "2_2") (pintype "passive"))
      (node (ref "R24") (pin "2") (pinfunction "2_2") (pintype "passive"))
      (node (ref "STM2") (pin "10") (pinfunction "VSS_10") (pintype "power_in"))
      (node (ref "STM2") (pin "20") (pinfunction "VSSA_20") (pintype "power_in"))
      (node (ref "STM2") (pin "27") (pinfunction "VSS_27") (pintype "power_in"))
      (node (ref "STM2") (pin "74") (pinfunction "VSS_74") (pintype "power_in"))
      (node (ref "STM2") (pin "99") (pinfunction "VSS_99") (pintype "power_in"))
      (node (ref "SW1") (pin "1") (pinfunction "1_1") (pintype "bidirectional"))
      (node (ref "Y2") (pin "2") (pinfunction "GND_2") (pintype "passive"))
      (node (ref "Y2") (pin "4") (pinfunction "GND_4") (pintype "passive"))
    )
    (net (code "88") (name "NOVA_3V3") (class "Default")
      (node (ref "C12") (pin "1") (pinfunction "1_1") (pintype "passive"))
      (node (ref "C13") (pin "1") (pinfunction "1_1") (pintype "passive"))
      (node (ref "C14") (pin "1") (pinfunction "1_1") (pintype "passive"))
      (node (ref "C15") (pin "1") (pinfunction "1_1") (pintype "passive"))
      (node (ref "C16") (pin "1") (pinfunction "1_1") (pintype "passive"))
      (node (ref "C17") (pin "1") (pinfunction "1_1") (pintype "passive"))
      (node (ref "C18") (pin "1") (pinfunction "1_1") (pintype "passive"))
      (node (ref "C19") (pin "2") (pinfunction "2_2") (pintype "passive"))
      (node (ref "C25") (pin "2") (pinfunction "2_2") (pintype "passive"))
      (node (ref "FB1") (pin "1") (pinfunction "1_1") (pintype "passive"))
      (node (ref "HLB1") (pin "23") (pinfunction "23_23") (pintype "passive"))
      (node (ref "HLT1") (pin "23") (pinfunction "23_23") (pintype "passive"))
      (node (ref "HRB1") (pin "21") (pinfunction "21_21") (pintype "passive"))
      (node (ref "HRB1") (pin "22") (pinfunction "22_22") (pintype "passive"))
      (node (ref "HRT1") (pin "20") (pinfunction "20_20") (pintype "passive"))
      (node (ref "HRT1") (pin "21") (pinfunction "21_21") (pintype "passive"))
      (node (ref "HRT1") (pin "22") (pinfunction "22_22") (pintype "passive"))
      (node (ref "IC2") (pin "2") (pinfunction "VOUT_2") (pintype "passive"))
      (node (ref "IC2") (pin "4") (pinfunction "VOUT_4") (pintype "passive"))
      (node (ref "Nova_B0") (pin "1") (pinfunction "1_1") (pintype "bidirectional"))
      (node (ref "Nova_B1") (pin "1") (pinfunction "1_1") (pintype "bidirectional"))
      (node (ref "PWR_D1") (pin "1") (pinfunction "1_1") (pintype "passive"))
      (node (ref "R18") (pin "1") (pinfunction "1_1") (pintype "passive"))
      (node (ref "STM2") (pin "100") (pinfunction "VDD_100") (pintype "power_in"))
      (node (ref "STM2") (pin "11") (pinfunction "VDD_11") (pintype "power_in"))
      (node (ref "STM2") (pin "19") (pinfunction "VDD_19") (pintype "power_in"))
      (node (ref "STM2") (pin "28") (pinfunction "VDD_28") (pintype "power_in"))
      (node (ref "STM2") (pin "50") (pinfunction "VDD_50") (pintype "power_in"))
      (node (ref "STM2") (pin "6") (pinfunction "VBAT_6") (pintype "power_in"))
      (node (ref "STM2") (pin "75") (pinfunction "VDD_75") (pintype "power_in"))
    )
    (net (code "89") (name "NOVA_5V") (class "Default")
      (node (ref "C23") (pin "1") (pinfunction "1_1") (pintype "passive"))
      (node (ref "C24") (pin "2") (pinfunction "2_2") (pintype "passive"))
      (node (ref "FB2") (pin "1") (pinfunction "1_1") (pintype "passive"))
      (node (ref "HLB1") (pin "22") (pinfunction "22_22") (pintype "passive"))
      (node (ref "HLT1") (pin "21") (pinfunction "21_21") (pintype "passive"))
      (node (ref "HLT1") (pin "22") (pinfunction "22_22") (pintype "passive"))
      (node (ref "HRB1") (pin "20") (pinfunction "20_20") (pintype "passive"))
      (node (ref "HRT1") (pin "19") (pinfunction "19_19") (pintype "passive"))
      (node (ref "IC2") (pin "3") (pinfunction "VIN_3") (pintype "passive"))
    )
    (net (code "90") (name "Net-(C21-Pad2)") (class "Default")
      (node (ref "C21") (pin "2") (pinfunction "2_2") (pintype "passive"))
      (node (ref "R16") (pin "1") (pinfunction "1_1") (pintype "passive"))
      (node (ref "Y2") (pin "3") (pinfunction "3_3") (pintype "passive"))
    )
    (net (code "91") (name "Net-(Nova_B0-Pad3)") (class "Default")
      (node (ref "Nova_B0") (pin "3") (pinfunction "3_3") (pintype "bidirectional"))
      (node (ref "R24") (pin "1") (pinfunction "1_1") (pintype "passive"))
    )
    (net (code "92") (name "Net-(Nova_B1-Pad3)") (class "Default")
      (node (ref "Nova_B1") (pin "3") (pinfunction "3_3") (pintype "bidirectional"))
      (node (ref "R23") (pin "1") (pinfunction "1_1") (pintype "passive"))
    )
    (net (code "93") (name "Net-(Nova_L0-Pad2)") (class "Default")
      (node (ref "Nova_L0") (pin "2") (pinfunction "2_2") (pintype "passive"))
      (node (ref "R19") (pin "2") (pinfunction "2_2") (pintype "passive"))
    )
    (net (code "94") (name "Net-(Nova_L1-Pad2)") (class "Default")
      (node (ref "Nova_L1") (pin "2") (pinfunction "2_2") (pintype "passive"))
      (node (ref "R20") (pin "2") (pinfunction "2_2") (pintype "passive"))
    )
    (net (code "95") (name "Net-(Nova_L2-Pad2)") (class "Default")
      (node (ref "Nova_L2") (pin "2") (pinfunction "2_2") (pintype "passive"))
      (node (ref "R21") (pin "2") (pinfunction "2_2") (pintype "passive"))
    )
    (net (code "96") (name "Net-(PWR_D1-Pad2)") (class "Default")
      (node (ref "PWR_D1") (pin "2") (pinfunction "2_2") (pintype "passive"))
      (node (ref "R22") (pin "1") (pinfunction "1_1") (pintype "passive"))
    )
    (net (code "97") (name "Net-(STM2-VCAP_1)") (class "Default")
      (node (ref "C29") (pin "1") (pinfunction "1_1") (pintype "passive"))
      (node (ref "STM2") (pin "49") (pinfunction "VCAP_1_49") (pintype "power_in"))
    )
    (net (code "98") (name "Net-(STM2-VCAP_2)") (class "Default")
      (node (ref "C30") (pin "1") (pinfunction "1_1") (pintype "passive"))
      (node (ref "STM2") (pin "73") (pinfunction "VCAP_2_73") (pintype "power_in"))
    )
    (net (code "99") (name "Net-(STM2-VREF+)") (class "Default")
      (node (ref "C27") (pin "1") (pinfunction "1_1") (pintype "passive"))
      (node (ref "C28") (pin "1") (pinfunction "1_1") (pintype "passive"))
      (node (ref "R25") (pin "2") (pinfunction "2_2") (pintype "passive"))
      (node (ref "STM2") (pin "21") (pinfunction "VREF+_21") (pintype "power_in"))
    )
    (net (code "100") (name "unconnected-(Nova_B0-Pad2)") (class "Default")
      (node (ref "Nova_B0") (pin "2") (pinfunction "2_2") (pintype "bidirectional+no_connect"))
    )
    (net (code "101") (name "unconnected-(Nova_B1-Pad2)") (class "Default")
      (node (ref "Nova_B1") (pin "2") (pinfunction "2_2") (pintype "bidirectional+no_connect"))
    )
    (net (code "102") (name "unconnected-(SW1-Pad2)") (class "Default")
      (node (ref "SW1") (pin "2") (pinfunction "2_2") (pintype "bidirectional+no_connect"))
    )
    (net (code "103") (name "unconnected-(SW1-Pad3)") (class "Default")
      (node (ref "SW1") (pin "3") (pinfunction "3_3") (pintype "bidirectional+no_connect"))
    )
  )
)
